# Line_Follower_Wrong.net
KiCad netlist of a schematic drawn in EAGLE
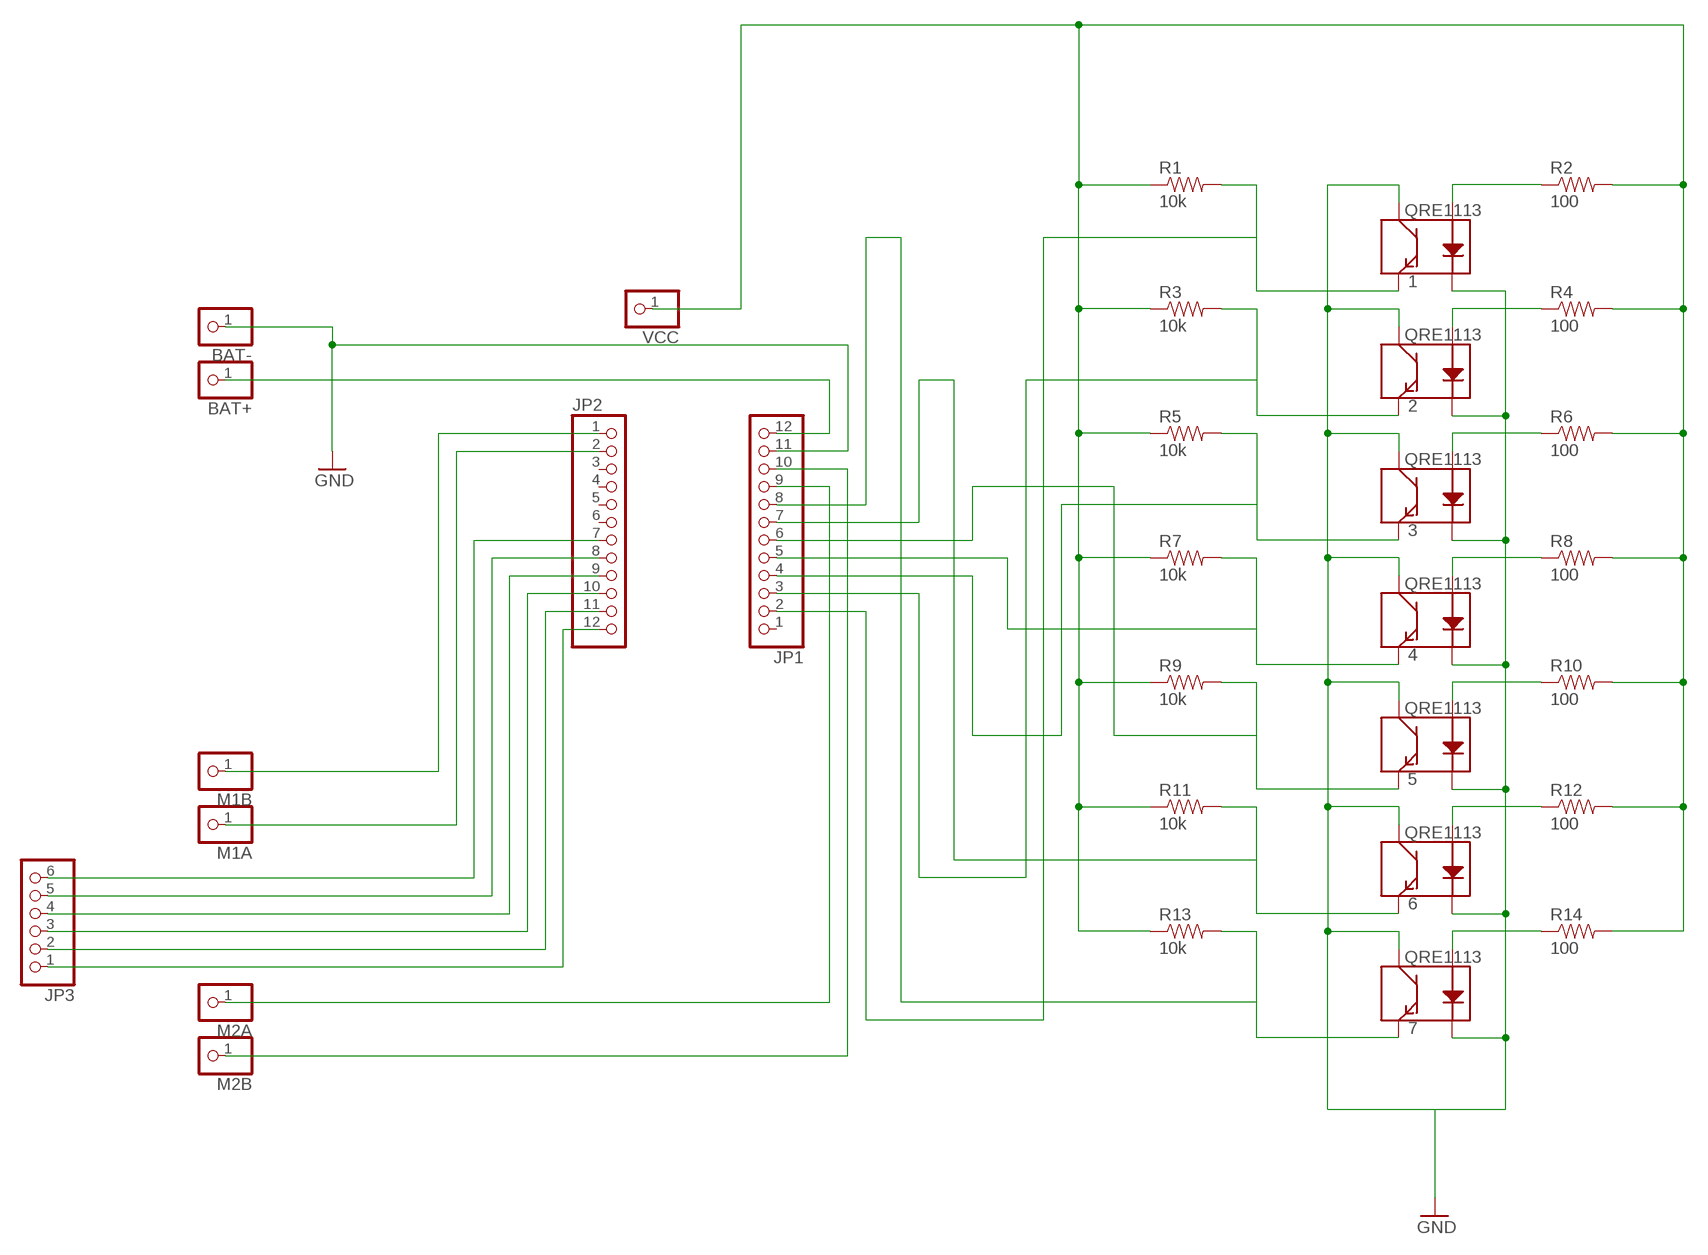
[diagram p0: schematic, sheet 1]

(export (version "E")
  (design (tool "Eeschema 10.0.6"))
  (components
    (comp (ref "1")
      (value "QRE1113")
      (footprint "eagle-import:QRE1113")
      (libsource (lib "eagle-import") (part "QRE1113"))
    )
    (comp (ref "2")
      (value "QRE1113")
      (footprint "eagle-import:QRE1113")
      (libsource (lib "eagle-import") (part "QRE1113"))
    )
    (comp (ref "3")
      (value "QRE1113")
      (footprint "eagle-import:QRE1113")
      (libsource (lib "eagle-import") (part "QRE1113"))
    )
    (comp (ref "4")
      (value "QRE1113")
      (footprint "eagle-import:QRE1113")
      (libsource (lib "eagle-import") (part "QRE1113"))
    )
    (comp (ref "5")
      (value "QRE1113")
      (footprint "eagle-import:QRE1113")
      (libsource (lib "eagle-import") (part "QRE1113"))
    )
    (comp (ref "6")
      (value "QRE1113")
      (footprint "eagle-import:QRE1113")
      (libsource (lib "eagle-import") (part "QRE1113"))
    )
    (comp (ref "7")
      (value "QRE1113")
      (footprint "eagle-import:QRE1113")
      (libsource (lib "eagle-import") (part "QRE1113"))
    )
    (comp (ref "BAT+")
      (value "PINHD-1X1")
      (footprint "eagle-import:1X01")
      (libsource (lib "eagle-import") (part "PINHD-1X1"))
    )
    (comp (ref "BAT-")
      (value "PINHD-1X1")
      (footprint "eagle-import:1X01")
      (libsource (lib "eagle-import") (part "PINHD-1X1"))
    )
    (comp (ref "JP1")
      (value "PINHD-1X12")
      (footprint "eagle-import:1X12")
      (libsource (lib "eagle-import") (part "PINHD-1X12"))
    )
    (comp (ref "JP2")
      (value "PINHD-1X12")
      (footprint "eagle-import:1X12")
      (libsource (lib "eagle-import") (part "PINHD-1X12"))
    )
    (comp (ref "JP3")
      (value "PINHD-1X6")
      (footprint "eagle-import:1X06")
      (libsource (lib "eagle-import") (part "PINHD-1X6"))
    )
    (comp (ref "M1A")
      (value "PINHD-1X1")
      (footprint "eagle-import:1X01")
      (libsource (lib "eagle-import") (part "PINHD-1X1"))
    )
    (comp (ref "M1B")
      (value "PINHD-1X1")
      (footprint "eagle-import:1X01")
      (libsource (lib "eagle-import") (part "PINHD-1X1"))
    )
    (comp (ref "M2A")
      (value "PINHD-1X1")
      (footprint "eagle-import:1X01")
      (libsource (lib "eagle-import") (part "PINHD-1X1"))
    )
    (comp (ref "M2B")
      (value "PINHD-1X1")
      (footprint "eagle-import:1X01")
      (libsource (lib "eagle-import") (part "PINHD-1X1"))
    )
    (comp (ref "R1")
      (value "10k")
      (footprint "eagle-import:0603-RES")
      (libsource (lib "eagle-import") (part "RESISTOR0603-RES"))
    )
    (comp (ref "R2")
      (value "100")
      (footprint "eagle-import:0805")
      (libsource (lib "eagle-import") (part "RESISTOR0805-RES"))
    )
    (comp (ref "R3")
      (value "10k")
      (footprint "eagle-import:0603-RES")
      (libsource (lib "eagle-import") (part "RESISTOR0603-RES"))
    )
    (comp (ref "R4")
      (value "100")
      (footprint "eagle-import:0805")
      (libsource (lib "eagle-import") (part "RESISTOR0805-RES"))
    )
    (comp (ref "R5")
      (value "10k")
      (footprint "eagle-import:0603-RES")
      (libsource (lib "eagle-import") (part "RESISTOR0603-RES"))
    )
    (comp (ref "R6")
      (value "100")
      (footprint "eagle-import:0805")
      (libsource (lib "eagle-import") (part "RESISTOR0805-RES"))
    )
    (comp (ref "R7")
      (value "10k")
      (footprint "eagle-import:0603-RES")
      (libsource (lib "eagle-import") (part "RESISTOR0603-RES"))
    )
    (comp (ref "R8")
      (value "100")
      (footprint "eagle-import:0805")
      (libsource (lib "eagle-import") (part "RESISTOR0805-RES"))
    )
    (comp (ref "R9")
      (value "10k")
      (footprint "eagle-import:0603-RES")
      (libsource (lib "eagle-import") (part "RESISTOR0603-RES"))
    )
    (comp (ref "R10")
      (value "100")
      (footprint "eagle-import:0805")
      (libsource (lib "eagle-import") (part "RESISTOR0805-RES"))
    )
    (comp (ref "R11")
      (value "10k")
      (footprint "eagle-import:0603-RES")
      (libsource (lib "eagle-import") (part "RESISTOR0603-RES"))
    )
    (comp (ref "R12")
      (value "100")
      (footprint "eagle-import:0805")
      (libsource (lib "eagle-import") (part "RESISTOR0805-RES"))
    )
    (comp (ref "R13")
      (value "10k")
      (footprint "eagle-import:0603-RES")
      (libsource (lib "eagle-import") (part "RESISTOR0603-RES"))
    )
    (comp (ref "R14")
      (value "100")
      (footprint "eagle-import:0805")
      (libsource (lib "eagle-import") (part "RESISTOR0805-RES"))
    )
    (comp (ref "VCC")
      (value "PINHD-1X1")
      (footprint "eagle-import:1X01")
      (libsource (lib "eagle-import") (part "PINHD-1X1"))
    )
  )
  (nets
    (net (code "1") (name "GND") (class "Default")
      (node (ref "1") (pin "2") (pinfunction "K_2") (pintype "bidirectional"))
      (node (ref "1") (pin "3") (pinfunction "C_3") (pintype "bidirectional"))
      (node (ref "2") (pin "2") (pinfunction "K_2") (pintype "bidirectional"))
      (node (ref "2") (pin "3") (pinfunction "C_3") (pintype "bidirectional"))
      (node (ref "3") (pin "2") (pinfunction "K_2") (pintype "bidirectional"))
      (node (ref "3") (pin "3") (pinfunction "C_3") (pintype "bidirectional"))
      (node (ref "4") (pin "2") (pinfunction "K_2") (pintype "bidirectional"))
      (node (ref "4") (pin "3") (pinfunction "C_3") (pintype "bidirectional"))
      (node (ref "5") (pin "2") (pinfunction "K_2") (pintype "bidirectional"))
      (node (ref "5") (pin "3") (pinfunction "C_3") (pintype "bidirectional"))
      (node (ref "6") (pin "2") (pinfunction "K_2") (pintype "bidirectional"))
      (node (ref "6") (pin "3") (pinfunction "C_3") (pintype "bidirectional"))
      (node (ref "7") (pin "2") (pinfunction "K_2") (pintype "bidirectional"))
      (node (ref "7") (pin "3") (pinfunction "C_3") (pintype "bidirectional"))
      (node (ref "BAT-") (pin "1") (pinfunction "1_1") (pintype "passive"))
      (node (ref "JP1") (pin "11") (pinfunction "11_11") (pintype "passive"))
    )
    (net (code "2") (name "Net-(1-A)") (class "Default")
      (node (ref "1") (pin "1") (pinfunction "A_1") (pintype "bidirectional"))
      (node (ref "R2") (pin "1") (pinfunction "1_1") (pintype "passive"))
    )
    (net (code "3") (name "Net-(1-E)") (class "Default")
      (node (ref "1") (pin "4") (pinfunction "E_4") (pintype "bidirectional"))
      (node (ref "JP1") (pin "2") (pinfunction "2_2") (pintype "passive"))
      (node (ref "R1") (pin "2") (pinfunction "2_2") (pintype "passive"))
    )
    (net (code "4") (name "Net-(2-A)") (class "Default")
      (node (ref "2") (pin "1") (pinfunction "A_1") (pintype "bidirectional"))
      (node (ref "R4") (pin "1") (pinfunction "1_1") (pintype "passive"))
    )
    (net (code "5") (name "Net-(2-E)") (class "Default")
      (node (ref "2") (pin "4") (pinfunction "E_4") (pintype "bidirectional"))
      (node (ref "JP1") (pin "3") (pinfunction "3_3") (pintype "passive"))
      (node (ref "R3") (pin "2") (pinfunction "2_2") (pintype "passive"))
    )
    (net (code "6") (name "Net-(3-A)") (class "Default")
      (node (ref "3") (pin "1") (pinfunction "A_1") (pintype "bidirectional"))
      (node (ref "R6") (pin "1") (pinfunction "1_1") (pintype "passive"))
    )
    (net (code "7") (name "Net-(3-E)") (class "Default")
      (node (ref "3") (pin "4") (pinfunction "E_4") (pintype "bidirectional"))
      (node (ref "JP1") (pin "4") (pinfunction "4_4") (pintype "passive"))
      (node (ref "R5") (pin "2") (pinfunction "2_2") (pintype "passive"))
    )
    (net (code "8") (name "Net-(4-A)") (class "Default")
      (node (ref "4") (pin "1") (pinfunction "A_1") (pintype "bidirectional"))
      (node (ref "R8") (pin "1") (pinfunction "1_1") (pintype "passive"))
    )
    (net (code "9") (name "Net-(4-E)") (class "Default")
      (node (ref "4") (pin "4") (pinfunction "E_4") (pintype "bidirectional"))
      (node (ref "JP1") (pin "5") (pinfunction "5_5") (pintype "passive"))
      (node (ref "R7") (pin "2") (pinfunction "2_2") (pintype "passive"))
    )
    (net (code "10") (name "Net-(5-A)") (class "Default")
      (node (ref "5") (pin "1") (pinfunction "A_1") (pintype "bidirectional"))
      (node (ref "R10") (pin "1") (pinfunction "1_1") (pintype "passive"))
    )
    (net (code "11") (name "Net-(5-E)") (class "Default")
      (node (ref "5") (pin "4") (pinfunction "E_4") (pintype "bidirectional"))
      (node (ref "JP1") (pin "6") (pinfunction "6_6") (pintype "passive"))
      (node (ref "R9") (pin "2") (pinfunction "2_2") (pintype "passive"))
    )
    (net (code "12") (name "Net-(6-A)") (class "Default")
      (node (ref "6") (pin "1") (pinfunction "A_1") (pintype "bidirectional"))
      (node (ref "R12") (pin "1") (pinfunction "1_1") (pintype "passive"))
    )
    (net (code "13") (name "Net-(6-E)") (class "Default")
      (node (ref "6") (pin "4") (pinfunction "E_4") (pintype "bidirectional"))
      (node (ref "JP1") (pin "7") (pinfunction "7_7") (pintype "passive"))
      (node (ref "R11") (pin "2") (pinfunction "2_2") (pintype "passive"))
    )
    (net (code "14") (name "Net-(7-A)") (class "Default")
      (node (ref "7") (pin "1") (pinfunction "A_1") (pintype "bidirectional"))
      (node (ref "R14") (pin "1") (pinfunction "1_1") (pintype "passive"))
    )
    (net (code "15") (name "Net-(7-E)") (class "Default")
      (node (ref "7") (pin "4") (pinfunction "E_4") (pintype "bidirectional"))
      (node (ref "JP1") (pin "8") (pinfunction "8_8") (pintype "passive"))
      (node (ref "R13") (pin "2") (pinfunction "2_2") (pintype "passive"))
    )
    (net (code "16") (name "Net-(BAT+-Pad1)") (class "Default")
      (node (ref "BAT+") (pin "1") (pinfunction "1_1") (pintype "passive"))
      (node (ref "JP1") (pin "12") (pinfunction "12_12") (pintype "passive"))
    )
    (net (code "17") (name "Net-(JP1-Pad9)") (class "Default")
      (node (ref "JP1") (pin "9") (pinfunction "9_9") (pintype "passive"))
      (node (ref "M2A") (pin "1") (pinfunction "1_1") (pintype "passive"))
    )
    (net (code "18") (name "Net-(JP1-Pad10)") (class "Default")
      (node (ref "JP1") (pin "10") (pinfunction "10_10") (pintype "passive"))
      (node (ref "M2B") (pin "1") (pinfunction "1_1") (pintype "passive"))
    )
    (net (code "19") (name "Net-(JP2-Pad1)") (class "Default")
      (node (ref "JP2") (pin "1") (pinfunction "1_1") (pintype "passive"))
      (node (ref "M1B") (pin "1") (pinfunction "1_1") (pintype "passive"))
    )
    (net (code "20") (name "Net-(JP2-Pad2)") (class "Default")
      (node (ref "JP2") (pin "2") (pinfunction "2_2") (pintype "passive"))
      (node (ref "M1A") (pin "1") (pinfunction "1_1") (pintype "passive"))
    )
    (net (code "21") (name "Net-(JP2-Pad7)") (class "Default")
      (node (ref "JP2") (pin "7") (pinfunction "7_7") (pintype "passive"))
      (node (ref "JP3") (pin "6") (pinfunction "6_6") (pintype "passive"))
    )
    (net (code "22") (name "Net-(JP2-Pad8)") (class "Default")
      (node (ref "JP2") (pin "8") (pinfunction "8_8") (pintype "passive"))
      (node (ref "JP3") (pin "5") (pinfunction "5_5") (pintype "passive"))
    )
    (net (code "23") (name "Net-(JP2-Pad9)") (class "Default")
      (node (ref "JP2") (pin "9") (pinfunction "9_9") (pintype "passive"))
      (node (ref "JP3") (pin "4") (pinfunction "4_4") (pintype "passive"))
    )
    (net (code "24") (name "Net-(JP2-Pad10)") (class "Default")
      (node (ref "JP2") (pin "10") (pinfunction "10_10") (pintype "passive"))
      (node (ref "JP3") (pin "3") (pinfunction "3_3") (pintype "passive"))
    )
    (net (code "25") (name "Net-(JP2-Pad11)") (class "Default")
      (node (ref "JP2") (pin "11") (pinfunction "11_11") (pintype "passive"))
      (node (ref "JP3") (pin "2") (pinfunction "2_2") (pintype "passive"))
    )
    (net (code "26") (name "Net-(JP2-Pad12)") (class "Default")
      (node (ref "JP2") (pin "12") (pinfunction "12_12") (pintype "passive"))
      (node (ref "JP3") (pin "1") (pinfunction "1_1") (pintype "passive"))
    )
    (net (code "27") (name "Net-(R1-Pad1)") (class "Default")
      (node (ref "R1") (pin "1") (pinfunction "1_1") (pintype "passive"))
      (node (ref "R10") (pin "2") (pinfunction "2_2") (pintype "passive"))
      (node (ref "R11") (pin "1") (pinfunction "1_1") (pintype "passive"))
      (node (ref "R12") (pin "2") (pinfunction "2_2") (pintype "passive"))
      (node (ref "R13") (pin "1") (pinfunction "1_1") (pintype "passive"))
      (node (ref "R14") (pin "2") (pinfunction "2_2") (pintype "passive"))
      (node (ref "R2") (pin "2") (pinfunction "2_2") (pintype "passive"))
      (node (ref "R3") (pin "1") (pinfunction "1_1") (pintype "passive"))
      (node (ref "R4") (pin "2") (pinfunction "2_2") (pintype "passive"))
      (node (ref "R5") (pin "1") (pinfunction "1_1") (pintype "passive"))
      (node (ref "R6") (pin "2") (pinfunction "2_2") (pintype "passive"))
      (node (ref "R7") (pin "1") (pinfunction "1_1") (pintype "passive"))
      (node (ref "R8") (pin "2") (pinfunction "2_2") (pintype "passive"))
      (node (ref "R9") (pin "1") (pinfunction "1_1") (pintype "passive"))
      (node (ref "VCC") (pin "1") (pinfunction "1_1") (pintype "passive"))
    )
    (net (code "28") (name "unconnected-(JP1-Pad1)") (class "Default")
      (node (ref "JP1") (pin "1") (pinfunction "1_1") (pintype "passive"))
    )
    (net (code "29") (name "unconnected-(JP2-Pad3)") (class "Default")
      (node (ref "JP2") (pin "3") (pinfunction "3_3") (pintype "passive"))
    )
    (net (code "30") (name "unconnected-(JP2-Pad4)") (class "Default")
      (node (ref "JP2") (pin "4") (pinfunction "4_4") (pintype "passive"))
    )
    (net (code "31") (name "unconnected-(JP2-Pad5)") (class "Default")
      (node (ref "JP2") (pin "5") (pinfunction "5_5") (pintype "passive"))
    )
    (net (code "32") (name "unconnected-(JP2-Pad6)") (class "Default")
      (node (ref "JP2") (pin "6") (pinfunction "6_6") (pintype "passive"))
    )
  )
)
